# ProDocument_BFMC_IMU.net
KiCad netlist of a schematic drawn in EasyEDA Pro
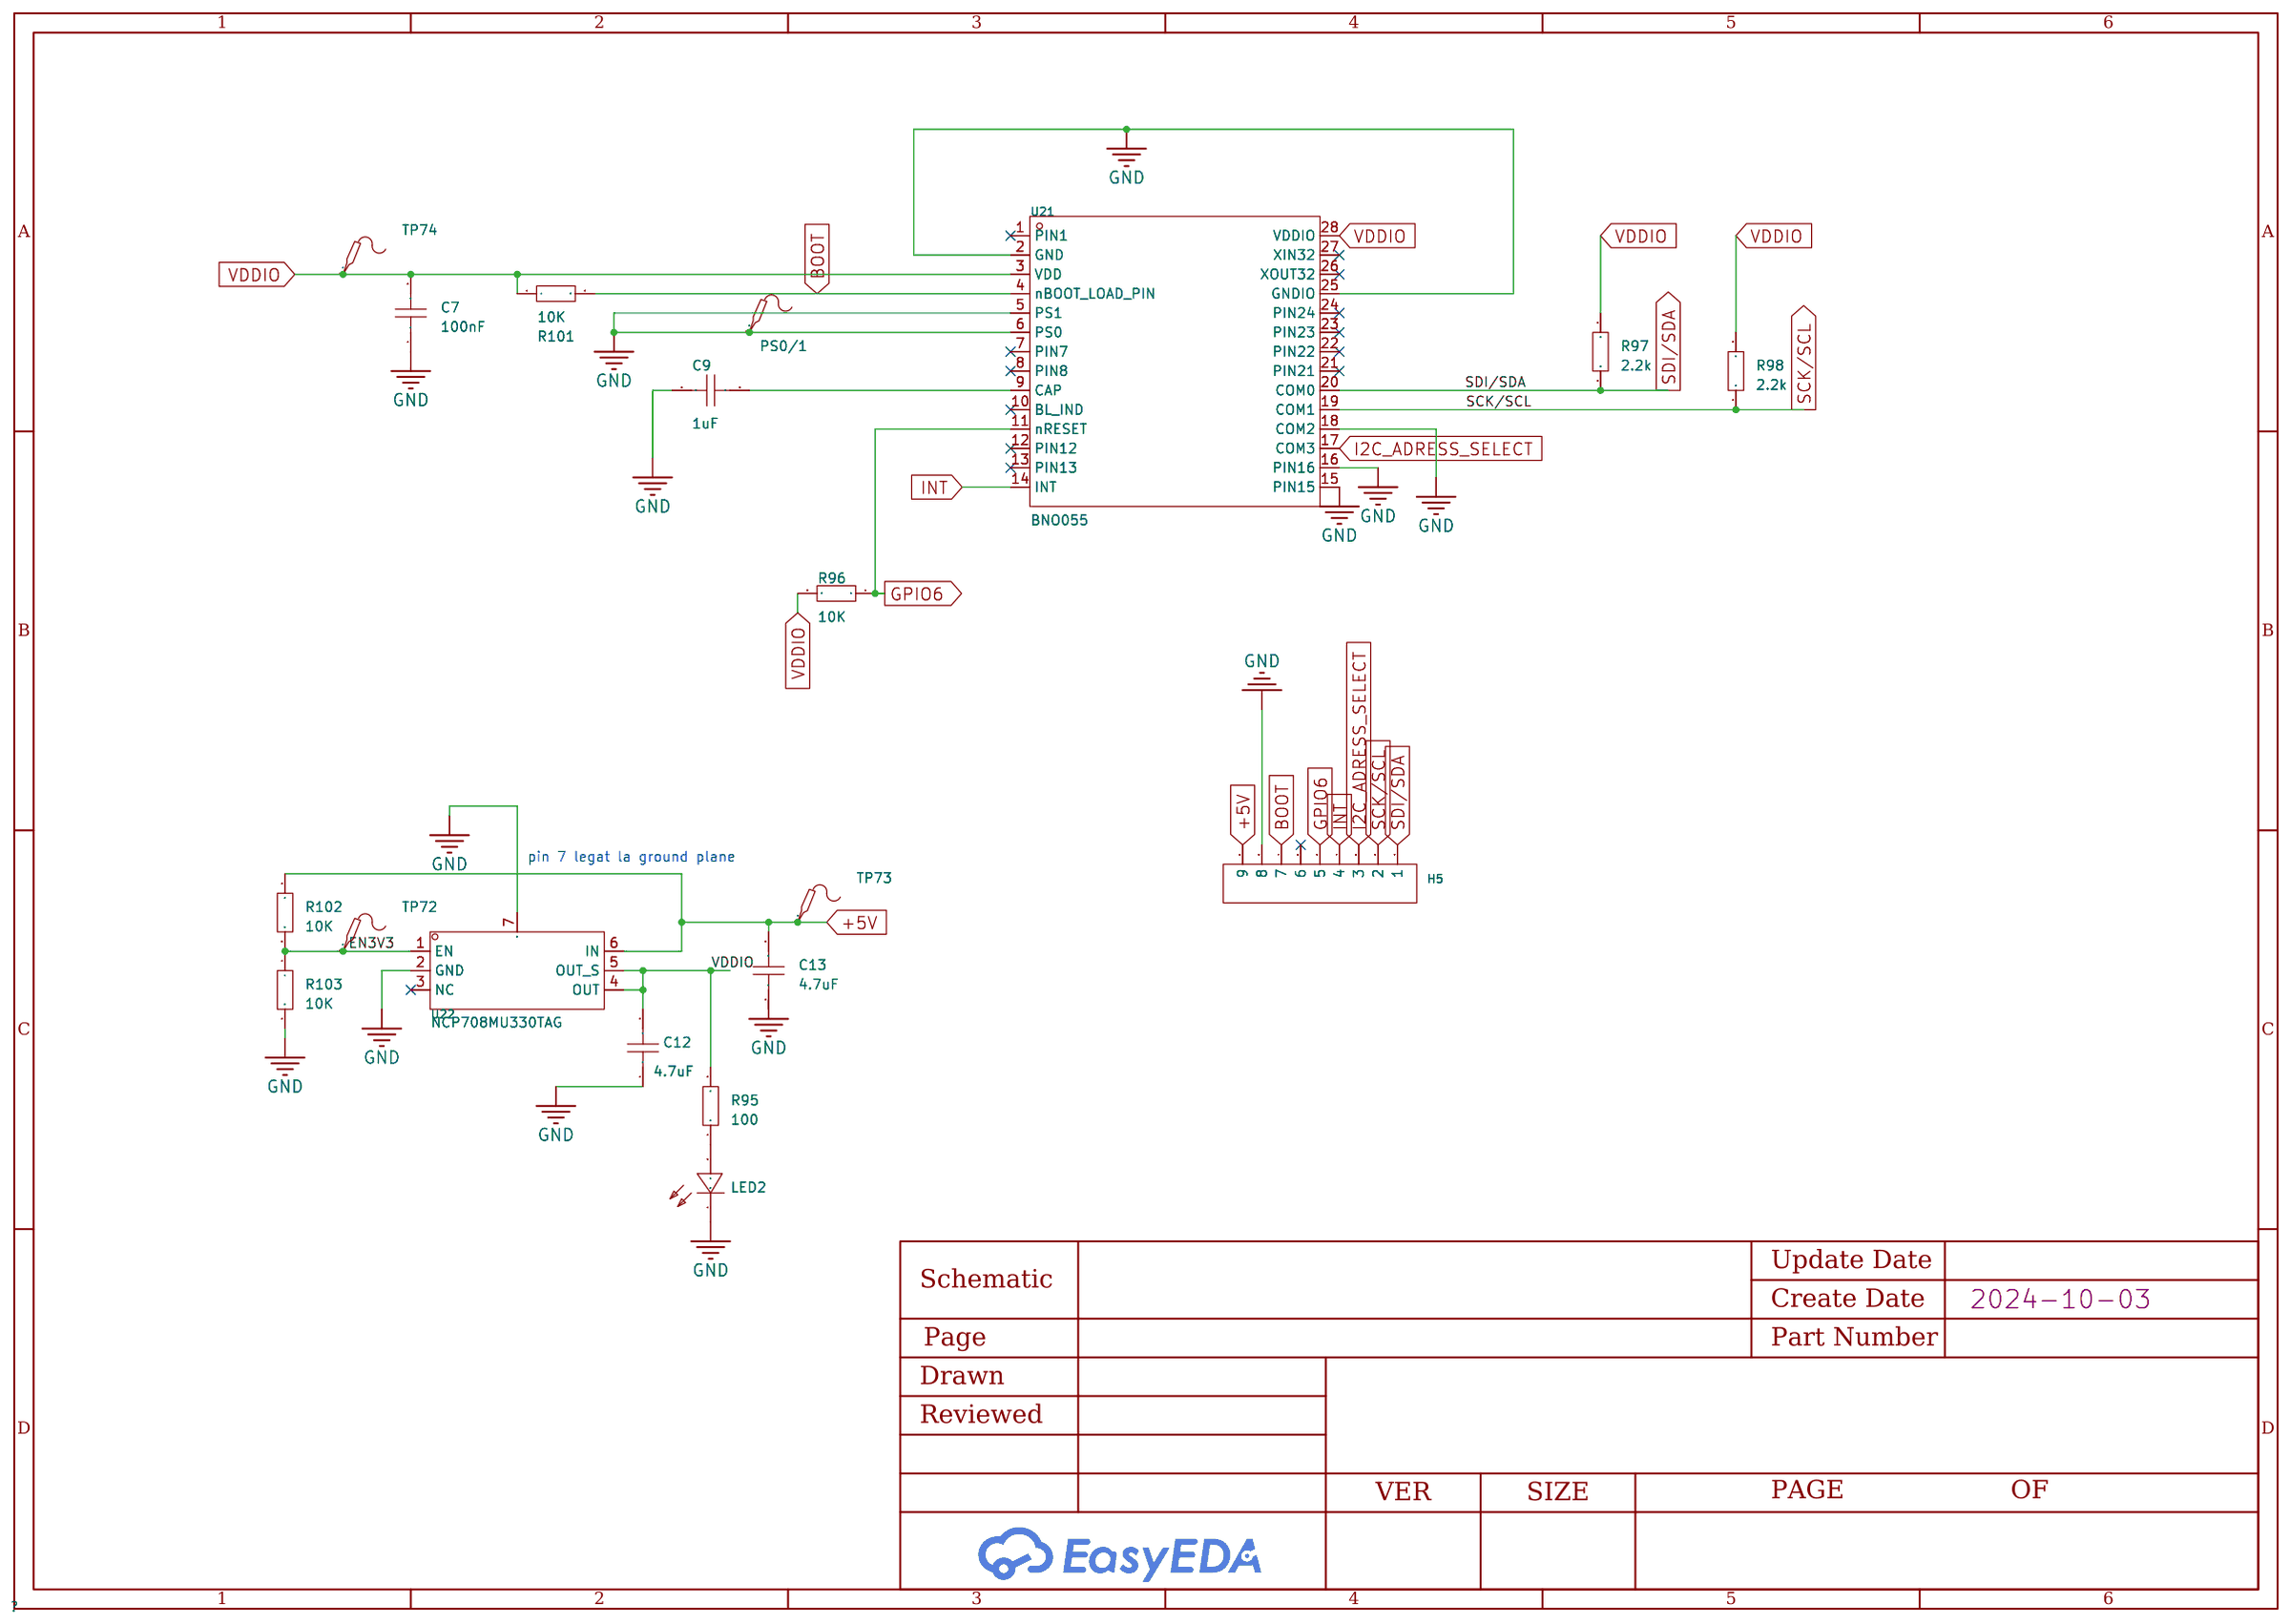
[diagram p0: schematic sheet]

(export (version "E")
  (design (tool "Eeschema 10.0.6"))
  (components
    (comp (ref "C7")
      (value "100nF")
      (footprint "easyedapro:C0201")
      (libsource (lib "easyedapro") (part "CAP"))
    )
    (comp (ref "C9") (value "1uF") (footprint "easyedapro:C0201") (libsource (lib "easyedapro") (part "CAP")))
    (comp (ref "C12")
      (value "4.7uF")
      (footprint "easyedapro:C0201")
      (libsource (lib "easyedapro") (part "CAP"))
    )
    (comp (ref "C13")
      (value "4.7uF")
      (footprint "easyedapro:C0201")
      (libsource (lib "easyedapro") (part "CAP"))
    )
    (comp (ref "H5")
      (value "~")
      (footprint "easyedapro:HDR-TH_9P-P2.54-V-F-1")
      (libsource (lib "easyedapro") (part "Header-Female-2.54_1x9"))
    )
    (comp (ref "LED2")
      (value "TLMS1100-GS08")
      (footprint "easyedapro:LED0603-RD_RED")
      (fields (field (name "Manufacturer") "VISHAY(威世)"))
      (libsource (lib "easyedapro") (part "TLMS1100-GS08"))
    )
    (comp (ref "PS0/1")
      (value "~")
      (footprint "easyedapro:Test-Point-0.5mm")
      (description "Test Point 测试点")
      (libsource (lib "easyedapro") (part "Test-Point"))
    )
    (comp (ref "R95")
      (value "100")
      (footprint "easyedapro:R0201")
      (libsource (lib "easyedapro") (part "Res"))
    )
    (comp (ref "R96")
      (value "10K")
      (footprint "easyedapro:R0201")
      (libsource (lib "easyedapro") (part "Res"))
    )
    (comp (ref "R97")
      (value "2.2k")
      (footprint "easyedapro:R0201")
      (libsource (lib "easyedapro") (part "Res"))
    )
    (comp (ref "R98")
      (value "2.2k")
      (footprint "easyedapro:R0201")
      (libsource (lib "easyedapro") (part "Res"))
    )
    (comp (ref "R101")
      (value "10K")
      (footprint "easyedapro:R0201")
      (libsource (lib "easyedapro") (part "Res"))
    )
    (comp (ref "R102")
      (value "10K")
      (footprint "easyedapro:R0201")
      (libsource (lib "easyedapro") (part "Res"))
    )
    (comp (ref "R103")
      (value "10K")
      (footprint "easyedapro:R0201")
      (libsource (lib "easyedapro") (part "Res"))
    )
    (comp (ref "TP72")
      (value "~")
      (footprint "easyedapro:Test-Point-0.5mm")
      (description "Test Point 测试点")
      (libsource (lib "easyedapro") (part "Test-Point"))
    )
    (comp (ref "TP73")
      (value "~")
      (footprint "easyedapro:Test-Point-0.5mm")
      (description "Test Point 测试点")
      (libsource (lib "easyedapro") (part "Test-Point"))
    )
    (comp (ref "TP74")
      (value "~")
      (footprint "easyedapro:Test-Point-0.5mm")
      (description "Test Point 测试点")
      (libsource (lib "easyedapro") (part "Test-Point"))
    )
    (comp (ref "U21")
      (value "BNO055")
      (footprint "easyedapro:LGA-28_L5.2-W3.8-P0.50-BL")
      (fields (field (name "Manufacturer") "Bosch(博世)"))
      (libsource (lib "easyedapro") (part "BNO055"))
    )
    (comp (ref "U22")
      (value "NCP708MU330TAG")
      (footprint "easyedapro:DFN-6_L3.0-W3.0-P0.95-LS3.1-BL-EP")
      (fields (field (name "Manufacturer") "onsemi(安森美)"))
      (libsource (lib "easyedapro") (part "NCP708MU330TAG"))
    )
  )
  (nets
    (net (code "1") (name "+5V") (class "Default")
      (node (ref "C13") (pin "2") (pinfunction "2_2") (pintype "input"))
      (node (ref "H5") (pin "9") (pinfunction "9_9") (pintype "input"))
      (node (ref "R102") (pin "1") (pinfunction "1_1") (pintype "input"))
      (node (ref "TP73") (pin "1") (pinfunction "1_1") (pintype "unspecified"))
      (node (ref "U22") (pin "6") (pinfunction "IN_6") (pintype "input"))
    )
    (net (code "2") (name "/EN3V3") (class "Default")
      (node (ref "R102") (pin "2") (pinfunction "2_2") (pintype "input"))
      (node (ref "R103") (pin "1") (pinfunction "1_1") (pintype "input"))
      (node (ref "TP72") (pin "1") (pinfunction "1_1") (pintype "unspecified"))
      (node (ref "U22") (pin "1") (pinfunction "EN_1") (pintype "input"))
    )
    (net (code "3") (name "BOOT") (class "Default")
      (node (ref "H5") (pin "7") (pinfunction "7_7") (pintype "input"))
      (node (ref "R101") (pin "2") (pinfunction "2_2") (pintype "input"))
      (node (ref "U21") (pin "4") (pinfunction "nBOOT_LOAD_PIN_4") (pintype "input"))
    )
    (net (code "4") (name "GND") (class "Default")
      (node (ref "C12") (pin "1") (pinfunction "1_1") (pintype "input"))
      (node (ref "C13") (pin "1") (pinfunction "1_1") (pintype "input"))
      (node (ref "C7") (pin "1") (pinfunction "1_1") (pintype "input"))
      (node (ref "C9") (pin "1") (pinfunction "1_1") (pintype "input"))
      (node (ref "H5") (pin "8") (pinfunction "8_8") (pintype "input"))
      (node (ref "LED2") (pin "1") (pinfunction "C_1") (pintype "unspecified"))
      (node (ref "PS0/1") (pin "1") (pinfunction "1_1") (pintype "unspecified"))
      (node (ref "R103") (pin "2") (pinfunction "2_2") (pintype "input"))
      (node (ref "U21") (pin "15") (pinfunction "PIN15_15") (pintype "input"))
      (node (ref "U21") (pin "16") (pinfunction "PIN16_16") (pintype "input"))
      (node (ref "U21") (pin "18") (pinfunction "COM2_18") (pintype "input"))
      (node (ref "U21") (pin "2") (pinfunction "GND_2") (pintype "input"))
      (node (ref "U21") (pin "25") (pinfunction "GNDIO_25") (pintype "input"))
      (node (ref "U21") (pin "5") (pinfunction "PS1_5") (pintype "input"))
      (node (ref "U21") (pin "6") (pinfunction "PS0_6") (pintype "input"))
      (node (ref "U22") (pin "2") (pinfunction "GND_2") (pintype "input"))
      (node (ref "U22") (pin "7") (pinfunction "PAD_7") (pintype "input"))
    )
    (net (code "5") (name "GPIO6") (class "Default")
      (node (ref "H5") (pin "5") (pinfunction "5_5") (pintype "input"))
      (node (ref "R96") (pin "1") (pinfunction "1_1") (pintype "input"))
      (node (ref "U21") (pin "11") (pinfunction "nRESET_11") (pintype "input"))
    )
    (net (code "6") (name "I2C_ADRESS_SELECT") (class "Default")
      (node (ref "H5") (pin "3") (pinfunction "3_3") (pintype "input"))
      (node (ref "U21") (pin "17") (pinfunction "COM3_17") (pintype "input"))
    )
    (net (code "7") (name "INT") (class "Default")
      (node (ref "H5") (pin "4") (pinfunction "4_4") (pintype "input"))
      (node (ref "U21") (pin "14") (pinfunction "INT_14") (pintype "input"))
    )
    (net (code "8") (name "Net-(LED2-A)") (class "Default")
      (node (ref "LED2") (pin "2") (pinfunction "A_2") (pintype "unspecified"))
      (node (ref "R95") (pin "1") (pinfunction "1_1") (pintype "input"))
    )
    (net (code "9") (name "Net-(U21-CAP)") (class "Default")
      (node (ref "C9") (pin "2") (pinfunction "2_2") (pintype "input"))
      (node (ref "U21") (pin "9") (pinfunction "CAP_9") (pintype "input"))
    )
    (net (code "10") (name "SCK{slash}SCL") (class "Default")
      (node (ref "H5") (pin "2") (pinfunction "2_2") (pintype "input"))
      (node (ref "R98") (pin "1") (pinfunction "1_1") (pintype "input"))
      (node (ref "U21") (pin "19") (pinfunction "COM1_19") (pintype "input"))
    )
    (net (code "11") (name "SDI{slash}SDA") (class "Default")
      (node (ref "H5") (pin "1") (pinfunction "1_1") (pintype "input"))
      (node (ref "R97") (pin "2") (pinfunction "2_2") (pintype "input"))
      (node (ref "U21") (pin "20") (pinfunction "COM0_20") (pintype "input"))
    )
    (net (code "12") (name "VDDIO") (class "Default")
      (node (ref "C12") (pin "2") (pinfunction "2_2") (pintype "input"))
      (node (ref "C7") (pin "2") (pinfunction "2_2") (pintype "input"))
      (node (ref "R101") (pin "1") (pinfunction "1_1") (pintype "input"))
      (node (ref "R95") (pin "2") (pinfunction "2_2") (pintype "input"))
      (node (ref "R96") (pin "2") (pinfunction "2_2") (pintype "input"))
      (node (ref "R97") (pin "1") (pinfunction "1_1") (pintype "input"))
      (node (ref "R98") (pin "2") (pinfunction "2_2") (pintype "input"))
      (node (ref "TP74") (pin "1") (pinfunction "1_1") (pintype "unspecified"))
      (node (ref "U21") (pin "28") (pinfunction "VDDIO_28") (pintype "input"))
      (node (ref "U21") (pin "3") (pinfunction "VDD_3") (pintype "input"))
      (node (ref "U22") (pin "4") (pinfunction "OUT_4") (pintype "input"))
      (node (ref "U22") (pin "5") (pinfunction "OUT_S_5") (pintype "input"))
    )
    (net (code "13") (name "unconnected-(H5-Pad6)") (class "Default")
      (node (ref "H5") (pin "6") (pinfunction "6_6") (pintype "input+no_connect"))
    )
    (net (code "14") (name "unconnected-(U21-BL_IND-Pad10)") (class "Default")
      (node (ref "U21") (pin "10") (pinfunction "BL_IND_10") (pintype "input+no_connect"))
    )
    (net (code "15") (name "unconnected-(U21-PIN1-Pad1)") (class "Default")
      (node (ref "U21") (pin "1") (pinfunction "PIN1_1") (pintype "input+no_connect"))
    )
    (net (code "16") (name "unconnected-(U21-PIN7-Pad7)") (class "Default")
      (node (ref "U21") (pin "7") (pinfunction "PIN7_7") (pintype "input+no_connect"))
    )
    (net (code "17") (name "unconnected-(U21-PIN8-Pad8)") (class "Default")
      (node (ref "U21") (pin "8") (pinfunction "PIN8_8") (pintype "input+no_connect"))
    )
    (net (code "18") (name "unconnected-(U21-PIN12-Pad12)") (class "Default")
      (node (ref "U21") (pin "12") (pinfunction "PIN12_12") (pintype "input+no_connect"))
    )
    (net (code "19") (name "unconnected-(U21-PIN13-Pad13)") (class "Default")
      (node (ref "U21") (pin "13") (pinfunction "PIN13_13") (pintype "input+no_connect"))
    )
    (net (code "20") (name "unconnected-(U21-PIN21-Pad21)") (class "Default")
      (node (ref "U21") (pin "21") (pinfunction "PIN21_21") (pintype "input+no_connect"))
    )
    (net (code "21") (name "unconnected-(U21-PIN22-Pad22)") (class "Default")
      (node (ref "U21") (pin "22") (pinfunction "PIN22_22") (pintype "input+no_connect"))
    )
    (net (code "22") (name "unconnected-(U21-PIN23-Pad23)") (class "Default")
      (node (ref "U21") (pin "23") (pinfunction "PIN23_23") (pintype "input+no_connect"))
    )
    (net (code "23") (name "unconnected-(U21-PIN24-Pad24)") (class "Default")
      (node (ref "U21") (pin "24") (pinfunction "PIN24_24") (pintype "input+no_connect"))
    )
    (net (code "24") (name "unconnected-(U21-XIN32-Pad27)") (class "Default")
      (node (ref "U21") (pin "27") (pinfunction "XIN32_27") (pintype "input+no_connect"))
    )
    (net (code "25") (name "unconnected-(U21-XOUT32-Pad26)") (class "Default")
      (node (ref "U21") (pin "26") (pinfunction "XOUT32_26") (pintype "input+no_connect"))
    )
    (net (code "26") (name "unconnected-(U22-NC-Pad3)") (class "Default")
      (node (ref "U22") (pin "3") (pinfunction "NC_3") (pintype "input+no_connect"))
    )
  )
)
